# ProiectTSC_v9.net
KiCad netlist of a schematic drawn in EAGLE
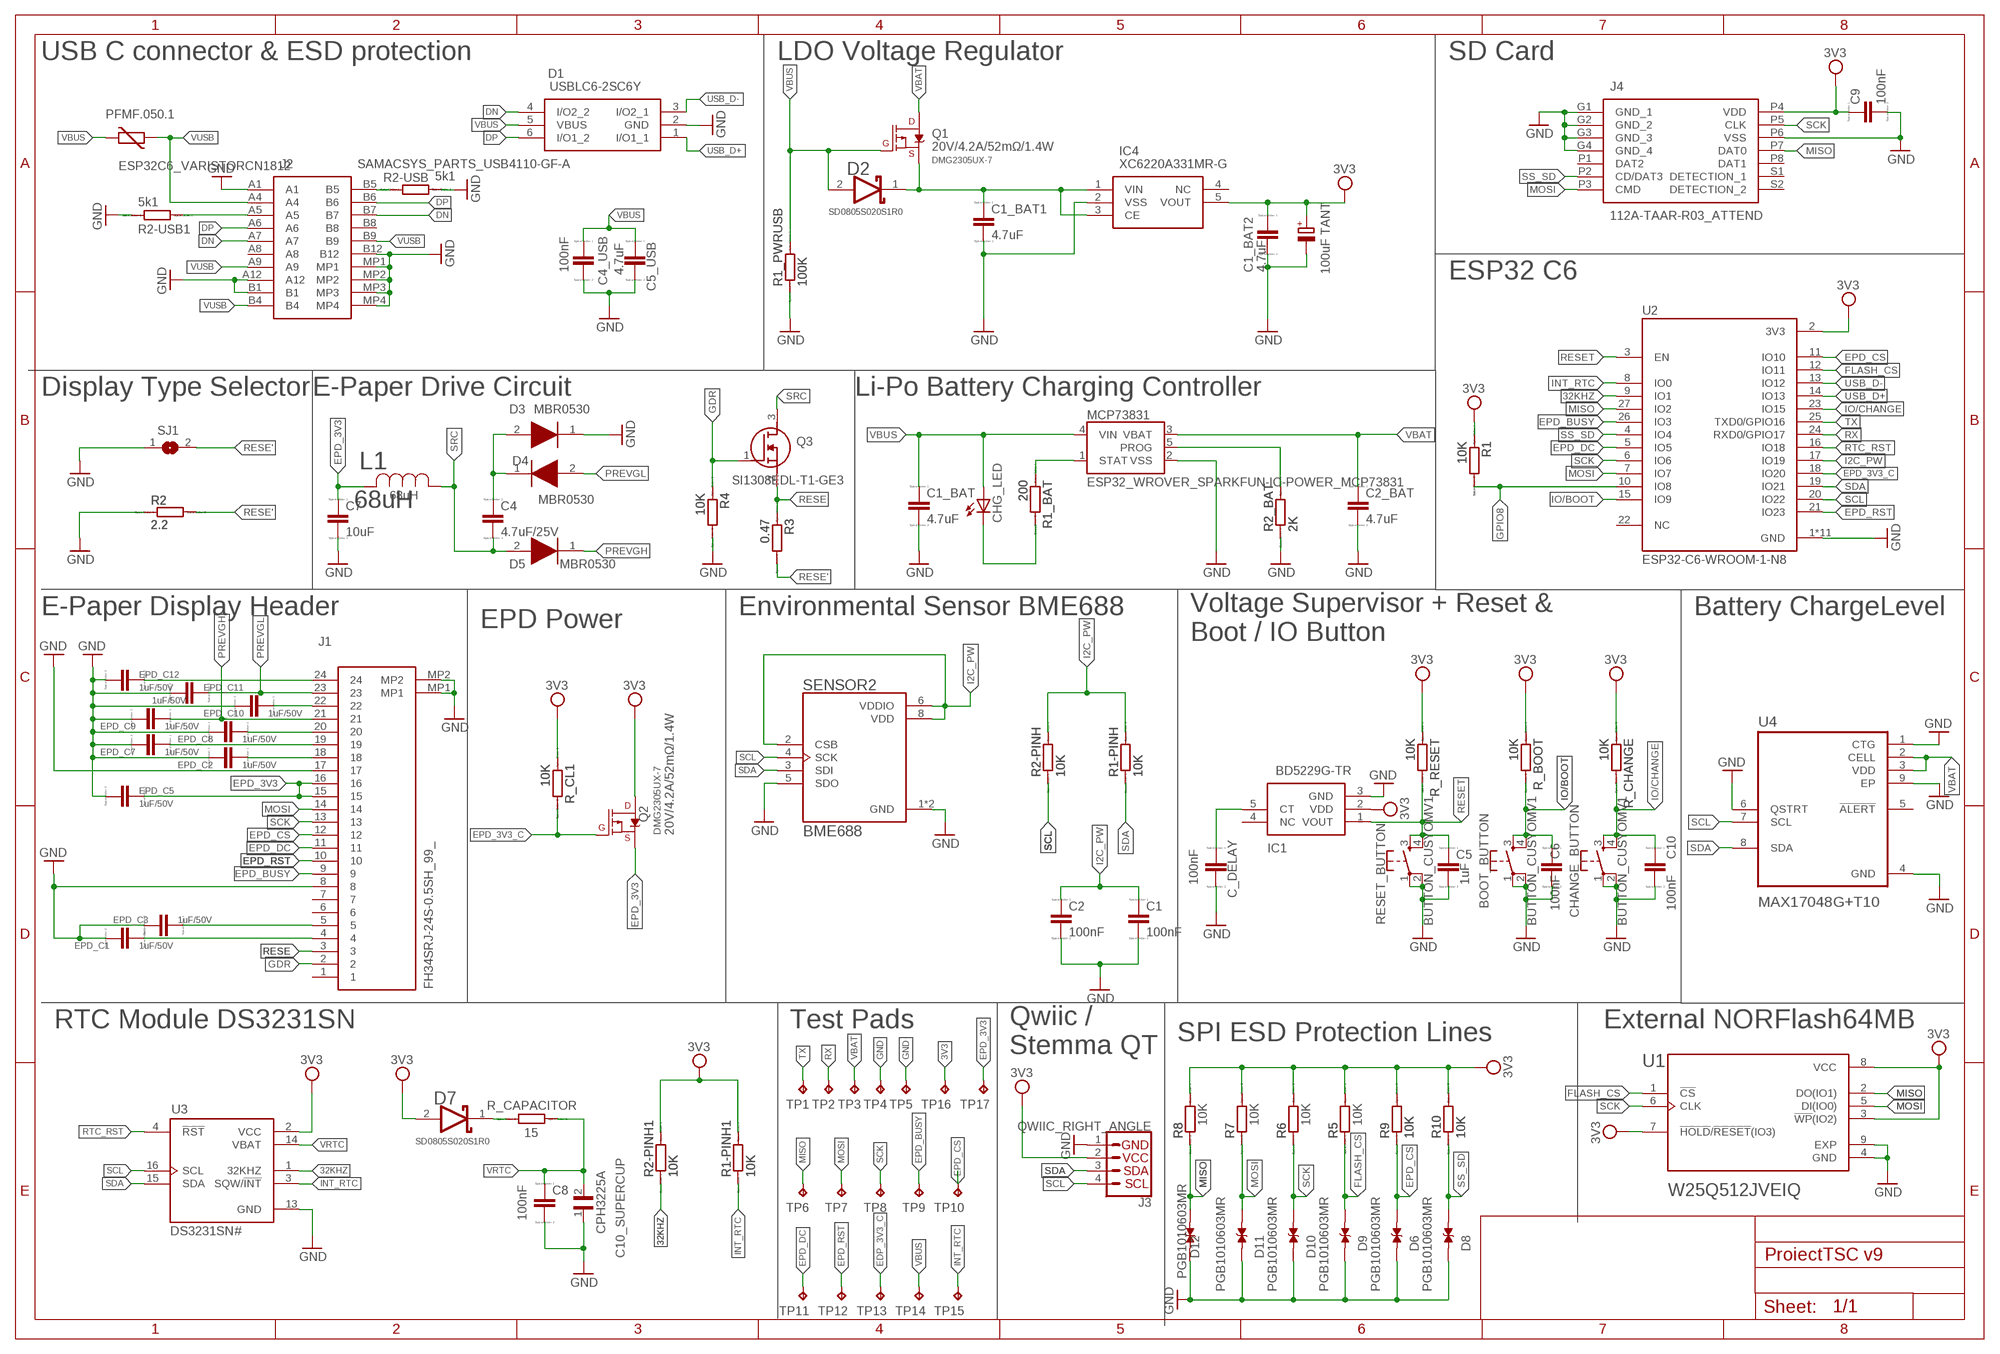
[diagram p0: schematic, sheet 1]

(export (version "E")
  (design (tool "Eeschema 10.0.6"))
  (components
    (comp (ref "BOOT_BUTTON")
      (value "BUTTON_CUSYOMV1")
      (footprint "eagle-import:MYBUTTON")
      (libsource (lib "eagle-import") (part "BUTTON_CUSYOMV1"))
    )
    (comp (ref "C1")
      (value "100nF")
      (footprint "eagle-import:EAGLE-LTSPICE_C0402")
      (libsource (lib "eagle-import") (part "EAGLE-LTSPICE_CC0402"))
    )
    (comp (ref "C1_BAT")
      (value "4.7uF")
      (footprint "eagle-import:EAGLE-LTSPICE_C0402")
      (libsource (lib "eagle-import") (part "EAGLE-LTSPICE_CC0402"))
    )
    (comp (ref "C1_BAT1")
      (value "4.7uF")
      (footprint "eagle-import:EAGLE-LTSPICE_C0402")
      (libsource (lib "eagle-import") (part "EAGLE-LTSPICE_CC0402"))
    )
    (comp (ref "C1_BAT2")
      (value "4.7uF")
      (footprint "eagle-import:EAGLE-LTSPICE_C0402")
      (libsource (lib "eagle-import") (part "EAGLE-LTSPICE_CC0402"))
    )
    (comp (ref "C2")
      (value "100nF")
      (footprint "eagle-import:EAGLE-LTSPICE_C0402")
      (libsource (lib "eagle-import") (part "EAGLE-LTSPICE_CC0402"))
    )
    (comp (ref "C2_BAT")
      (value "4.7uF")
      (footprint "eagle-import:EAGLE-LTSPICE_C0402")
      (libsource (lib "eagle-import") (part "EAGLE-LTSPICE_CC0402"))
    )
    (comp (ref "C4")
      (value "4.7uF/25V")
      (footprint "eagle-import:EAGLE-LTSPICE_C0402")
      (libsource (lib "eagle-import") (part "EAGLE-LTSPICE_CC0402"))
    )
    (comp (ref "C4_USB")
      (value "100nF")
      (footprint "eagle-import:EAGLE-LTSPICE_C0402")
      (libsource (lib "eagle-import") (part "EAGLE-LTSPICE_CC0402"))
    )
    (comp (ref "C5")
      (value "1uF")
      (footprint "eagle-import:EAGLE-LTSPICE_C0402")
      (libsource (lib "eagle-import") (part "EAGLE-LTSPICE_CC0402"))
    )
    (comp (ref "C5_USB")
      (value "4.7uF")
      (footprint "eagle-import:EAGLE-LTSPICE_C0402")
      (libsource (lib "eagle-import") (part "EAGLE-LTSPICE_CC0402"))
    )
    (comp (ref "C6")
      (value "100nF")
      (footprint "eagle-import:EAGLE-LTSPICE_C0402")
      (libsource (lib "eagle-import") (part "EAGLE-LTSPICE_CC0402"))
    )
    (comp (ref "C7")
      (value "10uF")
      (footprint "eagle-import:EAGLE-LTSPICE_C0402")
      (libsource (lib "eagle-import") (part "EAGLE-LTSPICE_CC0402"))
    )
    (comp (ref "C8")
      (value "100nF")
      (footprint "eagle-import:EAGLE-LTSPICE_C0402")
      (libsource (lib "eagle-import") (part "EAGLE-LTSPICE_CC0402"))
    )
    (comp (ref "C9")
      (value "100nF")
      (footprint "eagle-import:EAGLE-LTSPICE_C0402")
      (libsource (lib "eagle-import") (part "EAGLE-LTSPICE_CC0402"))
    )
    (comp (ref "C10")
      (value "100nF")
      (footprint "eagle-import:EAGLE-LTSPICE_C0402")
      (libsource (lib "eagle-import") (part "EAGLE-LTSPICE_CC0402"))
    )
    (comp (ref "C10_SUPERCUP")
      (value "CPH3225A")
      (footprint "eagle-import:CAPCP3225X100N")
      (fields (field (name "MF") "Seiko Instruments"))
      (libsource (lib "eagle-import") (part "CPH3225A"))
    )
    (comp (ref "CHANGE_BUTTON")
      (value "BUTTON_CUSYOMV1")
      (footprint "eagle-import:MYBUTTON")
      (libsource (lib "eagle-import") (part "BUTTON_CUSYOMV1"))
    )
    (comp (ref "CHG_LED")
      (value "ADAFRUIT_LEDCHIP-LED0603")
      (footprint "eagle-import:ADAFRUIT_CHIP-LED0603")
      (libsource (lib "eagle-import") (part "ADAFRUIT_LEDCHIP-LED0603"))
    )
    (comp (ref "C_DELAY")
      (value "100nF")
      (footprint "eagle-import:EAGLE-LTSPICE_C0402")
      (libsource (lib "eagle-import") (part "EAGLE-LTSPICE_CC0402"))
    )
    (comp (ref "D1")
      (value "USBLC6-2SC6Y")
      (footprint "eagle-import:SOT95P280X145-6N")
      (fields (field (name "MF") "STMicroelectronics"))
      (libsource (lib "eagle-import") (part "USBLC6-2SC6Y"))
    )
    (comp (ref "D2")
      (value "SD0805S020S1R0")
      (footprint "eagle-import:ESP32_WROVER_AVX---SD0805S020S1R0_AVX_SD0805S020S1R0_0")
      (fields
        (field (name "DIGIKEY_PART_NUMBER") "478-7800-1-ND")
        (field (name "MF") "AVX")
        (field (name "MOUSER_PART_NUMBER") "581-SD0805S020S1R0")
        (field (name "NUME") "SD0805S020S1R0")
      )
      (libsource (lib "eagle-import") (part "ESP32_WROVER_AVX---SD0805S020S1R0_AVX_SD0805S020S1R0_0_0AVX_SD0805S020S1R0_0_0"))
    )
    (comp (ref "D3")
      (value "MBR0530")
      (footprint "eagle-import:SOD3716X135N")
      (fields (field (name "MF") "ON Semiconductor"))
      (libsource (lib "eagle-import") (part "MBR0530"))
    )
    (comp (ref "D4")
      (value "MBR0530")
      (footprint "eagle-import:SOD3716X135N")
      (fields (field (name "MF") "ON Semiconductor"))
      (libsource (lib "eagle-import") (part "MBR0530"))
    )
    (comp (ref "D5")
      (value "MBR0530")
      (footprint "eagle-import:SOD3716X135N")
      (fields (field (name "MF") "ON Semiconductor"))
      (libsource (lib "eagle-import") (part "MBR0530"))
    )
    (comp (ref "D6")
      (value "PGB1010603MR")
      (footprint "eagle-import:DIOC1608X36N")
      (fields (field (name "MF") "Littelfuse Inc."))
      (libsource (lib "eagle-import") (part "PGB1010603MR"))
    )
    (comp (ref "D7")
      (value "SD0805S020S1R0")
      (footprint "eagle-import:ESP32_WROVER_AVX---SD0805S020S1R0_AVX_SD0805S020S1R0_0")
      (fields
        (field (name "DIGIKEY_PART_NUMBER") "478-7800-1-ND")
        (field (name "MF") "AVX")
        (field (name "MOUSER_PART_NUMBER") "581-SD0805S020S1R0")
        (field (name "MINE") "SD0805S020S1R0")
      )
      (libsource (lib "eagle-import") (part "ESP32_WROVER_AVX---SD0805S020S1R0_AVX_SD0805S020S1R0_0_0AVX_SD0805S020S1R0_0_0"))
    )
    (comp (ref "D8")
      (value "PGB1010603MR")
      (footprint "eagle-import:DIOC1608X36N")
      (fields (field (name "MF") "Littelfuse Inc."))
      (libsource (lib "eagle-import") (part "PGB1010603MR"))
    )
    (comp (ref "D9")
      (value "PGB1010603MR")
      (footprint "eagle-import:DIOC1608X36N")
      (fields (field (name "MF") "Littelfuse Inc."))
      (libsource (lib "eagle-import") (part "PGB1010603MR"))
    )
    (comp (ref "D10")
      (value "PGB1010603MR")
      (footprint "eagle-import:DIOC1608X36N")
      (fields (field (name "MF") "Littelfuse Inc."))
      (libsource (lib "eagle-import") (part "PGB1010603MR"))
    )
    (comp (ref "D11")
      (value "PGB1010603MR")
      (footprint "eagle-import:DIOC1608X36N")
      (fields (field (name "MF") "Littelfuse Inc."))
      (libsource (lib "eagle-import") (part "PGB1010603MR"))
    )
    (comp (ref "D12")
      (value "PGB1010603MR")
      (footprint "eagle-import:DIOC1608X36N")
      (fields (field (name "MF") "Littelfuse Inc."))
      (libsource (lib "eagle-import") (part "PGB1010603MR"))
    )
    (comp (ref "EPD_C1")
      (value "1uF/50V")
      (footprint "eagle-import:EAGLE-LTSPICE_C0402")
      (libsource (lib "eagle-import") (part "EAGLE-LTSPICE_CC0402"))
    )
    (comp (ref "EPD_C2")
      (value "1uF/50V")
      (footprint "eagle-import:EAGLE-LTSPICE_C0402")
      (libsource (lib "eagle-import") (part "EAGLE-LTSPICE_CC0402"))
    )
    (comp (ref "EPD_C3")
      (value "1uF/50V")
      (footprint "eagle-import:EAGLE-LTSPICE_C0402")
      (libsource (lib "eagle-import") (part "EAGLE-LTSPICE_CC0402"))
    )
    (comp (ref "EPD_C5")
      (value "1uF/50V")
      (footprint "eagle-import:EAGLE-LTSPICE_C0402")
      (libsource (lib "eagle-import") (part "EAGLE-LTSPICE_CC0402"))
    )
    (comp (ref "EPD_C7")
      (value "1uF/50V")
      (footprint "eagle-import:EAGLE-LTSPICE_C0402")
      (libsource (lib "eagle-import") (part "EAGLE-LTSPICE_CC0402"))
    )
    (comp (ref "EPD_C8")
      (value "1uF/50V")
      (footprint "eagle-import:EAGLE-LTSPICE_C0402")
      (libsource (lib "eagle-import") (part "EAGLE-LTSPICE_CC0402"))
    )
    (comp (ref "EPD_C9")
      (value "1uF/50V")
      (footprint "eagle-import:EAGLE-LTSPICE_C0402")
      (libsource (lib "eagle-import") (part "EAGLE-LTSPICE_CC0402"))
    )
    (comp (ref "EPD_C10")
      (value "1uF/50V")
      (footprint "eagle-import:EAGLE-LTSPICE_C0402")
      (libsource (lib "eagle-import") (part "EAGLE-LTSPICE_CC0402"))
    )
    (comp (ref "EPD_C11")
      (value "1uF/50V")
      (footprint "eagle-import:EAGLE-LTSPICE_C0402")
      (libsource (lib "eagle-import") (part "EAGLE-LTSPICE_CC0402"))
    )
    (comp (ref "EPD_C12")
      (value "1uF/50V")
      (footprint "eagle-import:EAGLE-LTSPICE_C0402")
      (libsource (lib "eagle-import") (part "EAGLE-LTSPICE_CC0402"))
    )
    (comp (ref "IC1")
      (value "BD5229G-TR")
      (footprint "eagle-import:SOT95P280X125-5N")
      (fields (field (name "MOUSER_PART_NUMBER") "755-BD5229G-TR"))
      (libsource (lib "eagle-import") (part "BD5229G-TR"))
    )
    (comp (ref "IC4")
      (value "XC6220A331MR-G")
      (footprint "eagle-import:SOT95P280X120-5N")
      (fields (field (name "MOUSER_PART_NUMBER") "865-XC6220A331MR-G"))
      (libsource (lib "eagle-import") (part "XC6220A331MR-G"))
    )
    (comp (ref "J1")
      (value "FH34SRJ-24S-0.5SH_99_")
      (footprint "eagle-import:FH34SRJ24S05SH99")
      (fields
        (field (name "MANUFACTURER_PART_NUMBER") "FH34SRJ-24S-0.5SH(99)")
        (field (name "MOUSER_PART_NUMBER") "798-FH34SRJ24S05SH99")
      )
      (libsource (lib "eagle-import") (part "FH34SRJ-24S-0.5SH_99_"))
    )
    (comp (ref "J2")
      (value "SAMACSYS_PARTS_USB4110-GF-A")
      (footprint "eagle-import:SAMACSYS_PARTS_USB4110GFA")
      (fields
        (field (name "MANUFACTURER_PART_NUMBER") "USB4110-GF-A")
        (field (name "MOUSER_PART_NUMBER") "640-USB4110-GF-A")
      )
      (libsource (lib "eagle-import") (part "SAMACSYS_PARTS_USB4110-GF-A"))
    )
    (comp (ref "J3")
      (value "QWIIC_RIGHT_ANGLE")
      (footprint "eagle-import:JST04_1MM_RA")
      (libsource (lib "eagle-import") (part "QWIIC_CONNECTORJS-1MM"))
    )
    (comp (ref "J4")
      (value "112A-TAAR-R03_ATTEND")
      (footprint "eagle-import:112ATAARR03ATTEND")
      (fields (field (name "MANUFACTURER_PART_NUMBER") "112A-TAAR-R03 ATTEND"))
      (libsource (lib "eagle-import") (part "112A-TAAR-R03_ATTEND"))
    )
    (comp (ref "L1")
      (value "68uH")
      (footprint "eagle-import:IND_4828-WE-TPC_WRE")
      (fields
        (field (name "MANUFACTURER_PART_NUMBER") "744043680")
        (field (name "NUME") "68uH")
        (field (name "COPYRIGHT") "Copyright (C) 2024 Ultra Librarian. All rights reserved.")
      )
      (libsource (lib "eagle-import") (part "744043680IND_4828-WE-TPC_WRE"))
    )
    (comp (ref "MCP73831")
      (value "ESP32_WROVER_SPARKFUN-IC-POWER_MCP73831")
      (footprint "eagle-import:ESP32_WROVER_SPARKFUN-IC-POWER_SOT23-5")
      (libsource (lib "eagle-import") (part "ESP32_WROVER_SPARKFUN-IC-POWER_MCP73831"))
    )
    (comp (ref "PFMF.050.1")
      (value "ESP32C6_VARISTORCN1812")
      (footprint "eagle-import:ESP32C6_VARISTOR_CT_CN1812")
      (libsource (lib "eagle-import") (part "ESP32C6_VARISTORCN1812"))
    )
    (comp (ref "Q1")
      (value "20V/4.2A/52mΩ/1.4W")
      (footprint "eagle-import:ESP32_WROVER_SPARKFUN-DISCRETESEMI_SOT23-3")
      (fields (field (name "NUME") "DMG2305UX-7"))
      (libsource (lib "eagle-import") (part "ESP32_WROVER_SPARKFUN-DISCRETESEMI_MOSFET_PCH-DMG2305UX-7"))
    )
    (comp (ref "Q2")
      (value "20V/4.2A/52mΩ/1.4W")
      (footprint "eagle-import:ESP32_WROVER_SPARKFUN-DISCRETESEMI_SOT23-3")
      (fields (field (name "MINE") "DMG2305UX-7"))
      (libsource (lib "eagle-import") (part "ESP32_WROVER_SPARKFUN-DISCRETESEMI_MOSFET_PCH-DMG2305UX-7"))
    )
    (comp (ref "Q3")
      (value "SI1308EDL-T1-GE3")
      (footprint "eagle-import:SOT65P210X110-3N")
      (fields (field (name "MF") "Vishay Siliconix"))
      (libsource (lib "eagle-import") (part "SI1308EDL-T1-GE3"))
    )
    (comp (ref "R1")
      (value "10K")
      (footprint "eagle-import:ESP32_WROVER_EAGLE-LTSPICE_R0402")
      (libsource (lib "eagle-import") (part "ESP32_WROVER_EAGLE-LTSPICE_RR0402"))
    )
    (comp (ref "R1-PINH")
      (value "10K")
      (footprint "eagle-import:ESP32_WROVER_EAGLE-LTSPICE_R0402")
      (libsource (lib "eagle-import") (part "ESP32_WROVER_EAGLE-LTSPICE_RR0402"))
    )
    (comp (ref "R1-PINH1")
      (value "10K")
      (footprint "eagle-import:ESP32_WROVER_EAGLE-LTSPICE_R0402")
      (libsource (lib "eagle-import") (part "ESP32_WROVER_EAGLE-LTSPICE_RR0402"))
    )
    (comp (ref "R1_BAT")
      (value "200")
      (footprint "eagle-import:ESP32_WROVER_EAGLE-LTSPICE_R0402")
      (libsource (lib "eagle-import") (part "ESP32_WROVER_EAGLE-LTSPICE_RR0402"))
    )
    (comp (ref "R1_PWRUSB")
      (value "100K")
      (footprint "eagle-import:ESP32_WROVER_EAGLE-LTSPICE_R0402")
      (libsource (lib "eagle-import") (part "ESP32_WROVER_EAGLE-LTSPICE_RR0402"))
    )
    (comp (ref "R2")
      (value "2.2")
      (footprint "eagle-import:ESP32_WROVER_EAGLE-LTSPICE_R0402")
      (libsource (lib "eagle-import") (part "ESP32_WROVER_EAGLE-LTSPICE_RR0402"))
    )
    (comp (ref "R2-PINH")
      (value "10K")
      (footprint "eagle-import:ESP32_WROVER_EAGLE-LTSPICE_R0402")
      (libsource (lib "eagle-import") (part "ESP32_WROVER_EAGLE-LTSPICE_RR0402"))
    )
    (comp (ref "R2-PINH1")
      (value "10K")
      (footprint "eagle-import:ESP32_WROVER_EAGLE-LTSPICE_R0402")
      (libsource (lib "eagle-import") (part "ESP32_WROVER_EAGLE-LTSPICE_RR0402"))
    )
    (comp (ref "R2-USB")
      (value "5k1")
      (footprint "eagle-import:ESP32_WROVER_EAGLE-LTSPICE_R0402")
      (libsource (lib "eagle-import") (part "ESP32_WROVER_EAGLE-LTSPICE_RR0402"))
    )
    (comp (ref "R2-USB1")
      (value "5k1")
      (footprint "eagle-import:ESP32_WROVER_EAGLE-LTSPICE_R0402")
      (libsource (lib "eagle-import") (part "ESP32_WROVER_EAGLE-LTSPICE_RR0402"))
    )
    (comp (ref "R2_BAT")
      (value "2K")
      (footprint "eagle-import:ESP32_WROVER_EAGLE-LTSPICE_R0402")
      (libsource (lib "eagle-import") (part "ESP32_WROVER_EAGLE-LTSPICE_RR0402"))
    )
    (comp (ref "R3")
      (value "0.47")
      (footprint "eagle-import:ESP32_WROVER_EAGLE-LTSPICE_R0402")
      (libsource (lib "eagle-import") (part "ESP32_WROVER_EAGLE-LTSPICE_RR0402"))
    )
    (comp (ref "R4")
      (value "10K")
      (footprint "eagle-import:ESP32_WROVER_EAGLE-LTSPICE_R0402")
      (libsource (lib "eagle-import") (part "ESP32_WROVER_EAGLE-LTSPICE_RR0402"))
    )
    (comp (ref "R5")
      (value "10K")
      (footprint "eagle-import:ESP32_WROVER_EAGLE-LTSPICE_R0402")
      (libsource (lib "eagle-import") (part "ESP32_WROVER_EAGLE-LTSPICE_RR0402"))
    )
    (comp (ref "R6")
      (value "10K")
      (footprint "eagle-import:ESP32_WROVER_EAGLE-LTSPICE_R0402")
      (libsource (lib "eagle-import") (part "ESP32_WROVER_EAGLE-LTSPICE_RR0402"))
    )
    (comp (ref "R7")
      (value "10K")
      (footprint "eagle-import:ESP32_WROVER_EAGLE-LTSPICE_R0402")
      (libsource (lib "eagle-import") (part "ESP32_WROVER_EAGLE-LTSPICE_RR0402"))
    )
    (comp (ref "R8")
      (value "10K")
      (footprint "eagle-import:ESP32_WROVER_EAGLE-LTSPICE_R0402")
      (libsource (lib "eagle-import") (part "ESP32_WROVER_EAGLE-LTSPICE_RR0402"))
    )
    (comp (ref "R9")
      (value "10K")
      (footprint "eagle-import:ESP32_WROVER_EAGLE-LTSPICE_R0402")
      (libsource (lib "eagle-import") (part "ESP32_WROVER_EAGLE-LTSPICE_RR0402"))
    )
    (comp (ref "R10")
      (value "10K")
      (footprint "eagle-import:ESP32_WROVER_EAGLE-LTSPICE_R0402")
      (libsource (lib "eagle-import") (part "ESP32_WROVER_EAGLE-LTSPICE_RR0402"))
    )
    (comp (ref "RESET_BUTTON")
      (value "BUTTON_CUSYOMV1")
      (footprint "eagle-import:MYBUTTON")
      (libsource (lib "eagle-import") (part "BUTTON_CUSYOMV1"))
    )
    (comp (ref "R_BOOT")
      (value "10K")
      (footprint "eagle-import:ESP32_WROVER_EAGLE-LTSPICE_R0402")
      (libsource (lib "eagle-import") (part "ESP32_WROVER_EAGLE-LTSPICE_RR0402"))
    )
    (comp (ref "R_CAPACITOR")
      (value "15")
      (footprint "eagle-import:ESP32_WROVER_EAGLE-LTSPICE_R0402")
      (libsource (lib "eagle-import") (part "ESP32_WROVER_EAGLE-LTSPICE_RR0402"))
    )
    (comp (ref "R_CHANGE")
      (value "10K")
      (footprint "eagle-import:ESP32_WROVER_EAGLE-LTSPICE_R0402")
      (libsource (lib "eagle-import") (part "ESP32_WROVER_EAGLE-LTSPICE_RR0402"))
    )
    (comp (ref "R_CL1")
      (value "10K")
      (footprint "eagle-import:ESP32_WROVER_EAGLE-LTSPICE_R0402")
      (libsource (lib "eagle-import") (part "ESP32_WROVER_EAGLE-LTSPICE_RR0402"))
    )
    (comp (ref "R_RESET")
      (value "10K")
      (footprint "eagle-import:ESP32_WROVER_EAGLE-LTSPICE_R0402")
      (libsource (lib "eagle-import") (part "ESP32_WROVER_EAGLE-LTSPICE_RR0402"))
    )
    (comp (ref "SENSOR2")
      (value "BME688")
      (footprint "eagle-import:ESP32_WROVER_BME680_PSON80P300X300X100-8N")
      (fields (field (name "MF") "Bosch Sensortec") (field (name "MP") "BME680"))
      (libsource (lib "eagle-import") (part "ESP32_WROVER_BME680_BME680"))
    )
    (comp (ref "SJ1") (value "SJ") (footprint "eagle-import:SJ") (libsource (lib "eagle-import") (part "SJ")))
    (comp (ref "TANT")
      (value "100uF")
      (footprint "eagle-import:RCL_CT3528")
      (libsource (lib "eagle-import") (part "RCL_CPOL-EUCT3528"))
    )
    (comp (ref "TP1")
      (value "TPTP20R")
      (footprint "eagle-import:TP20R")
      (libsource (lib "eagle-import") (part "TPTP20R"))
    )
    (comp (ref "TP2")
      (value "TPTP20R")
      (footprint "eagle-import:TP20R")
      (libsource (lib "eagle-import") (part "TPTP20R"))
    )
    (comp (ref "TP3")
      (value "TPTP20R")
      (footprint "eagle-import:TP20R")
      (libsource (lib "eagle-import") (part "TPTP20R"))
    )
    (comp (ref "TP4")
      (value "TPTP20R")
      (footprint "eagle-import:TP20R")
      (libsource (lib "eagle-import") (part "TPTP20R"))
    )
    (comp (ref "TP5")
      (value "TPTP20R")
      (footprint "eagle-import:TP20R")
      (libsource (lib "eagle-import") (part "TPTP20R"))
    )
    (comp (ref "TP6")
      (value "TPTP20R")
      (footprint "eagle-import:TP20R")
      (libsource (lib "eagle-import") (part "TPTP20R"))
    )
    (comp (ref "TP7")
      (value "TPTP20R")
      (footprint "eagle-import:TP20R")
      (libsource (lib "eagle-import") (part "TPTP20R"))
    )
    (comp (ref "TP8")
      (value "TPTP20R")
      (footprint "eagle-import:TP20R")
      (libsource (lib "eagle-import") (part "TPTP20R"))
    )
    (comp (ref "TP9")
      (value "TPTP20R")
      (footprint "eagle-import:TP20R")
      (libsource (lib "eagle-import") (part "TPTP20R"))
    )
    (comp (ref "TP10")
      (value "TPTP20R")
      (footprint "eagle-import:TP20R")
      (libsource (lib "eagle-import") (part "TPTP20R"))
    )
    (comp (ref "TP11")
      (value "TPTP20R")
      (footprint "eagle-import:TP20R")
      (libsource (lib "eagle-import") (part "TPTP20R"))
    )
    (comp (ref "TP12")
      (value "TPTP20R")
      (footprint "eagle-import:TP20R")
      (libsource (lib "eagle-import") (part "TPTP20R"))
    )
    (comp (ref "TP13")
      (value "TPTP20R")
      (footprint "eagle-import:TP20R")
      (libsource (lib "eagle-import") (part "TPTP20R"))
    )
    (comp (ref "TP14")
      (value "TPTP20R")
      (footprint "eagle-import:TP20R")
      (libsource (lib "eagle-import") (part "TPTP20R"))
    )
    (comp (ref "TP15")
      (value "TPTP20R")
      (footprint "eagle-import:TP20R")
      (libsource (lib "eagle-import") (part "TPTP20R"))
    )
    (comp (ref "TP16")
      (value "TPTP20R")
      (footprint "eagle-import:TP20R")
      (libsource (lib "eagle-import") (part "TPTP20R"))
    )
    (comp (ref "TP17")
      (value "TPTP20R")
      (footprint "eagle-import:TP20R")
      (libsource (lib "eagle-import") (part "TPTP20R"))
    )
    (comp (ref "U1")
      (value "W25Q512JVEIQ")
      (footprint "eagle-import:SON127P600X800X80-9N")
      (fields (field (name "MF") "Winbond Electronics"))
      (libsource (lib "eagle-import") (part "W25Q512JVEIQ"))
    )
    (comp (ref "U2")
      (value "ESP32-C6-WROOM-1-N8")
      (footprint "eagle-import:XCVR_ESP32-C6-WROOM-1-N8")
      (fields (field (name "MF") "Espressif Systems"))
      (libsource (lib "eagle-import") (part "ESP32-C6-WROOM-1-N8"))
    )
    (comp (ref "U3")
      (value "DS3231SN#")
      (footprint "eagle-import:SOIC127P1032X265-16N")
      (fields (field (name "MF") "Analog Devices"))
      (libsource (lib "eagle-import") (part "DS3231SN#"))
    )
    (comp (ref "U4")
      (value "MAX17048G+T10")
      (footprint "eagle-import:SON50P200X200X80-9N")
      (fields (field (name "MF") "Analog Devices"))
      (libsource (lib "eagle-import") (part "MAX17048G+T10"))
    )
  )
  (nets
    (net (code "1") (name "3V3") (class "Default")
      (node (ref "C1_BAT2") (pin "1") (pinfunction "1_1") (pintype "passive"))
      (node (ref "C9") (pin "1") (pinfunction "1_1") (pintype "passive"))
      (node (ref "D7") (pin "2") (pinfunction "ANODE_2") (pintype "bidirectional"))
      (node (ref "IC1") (pin "2") (pinfunction "VDD_2") (pintype "bidirectional"))
      (node (ref "IC4") (pin "5") (pinfunction "VOUT_5") (pintype "bidirectional"))
      (node (ref "J3") (pin "2") (pinfunction "2_2") (pintype "power_in"))
      (node (ref "J4") (pin "P4") (pinfunction "VDD_P4") (pintype "bidirectional"))
      (node (ref "Q2") (pin "3") (pinfunction "D_3") (pintype "bidirectional"))
      (node (ref "R1") (pin "1") (pinfunction "1_1") (pintype "passive"))
      (node (ref "R1-PINH1") (pin "2") (pinfunction "2_2") (pintype "passive"))
      (node (ref "R10") (pin "2") (pinfunction "2_2") (pintype "passive"))
      (node (ref "R2-PINH1") (pin "2") (pinfunction "2_2") (pintype "passive"))
      (node (ref "R5") (pin "2") (pinfunction "2_2") (pintype "passive"))
      (node (ref "R6") (pin "2") (pinfunction "2_2") (pintype "passive"))
      (node (ref "R7") (pin "2") (pinfunction "2_2") (pintype "passive"))
      (node (ref "R8") (pin "2") (pinfunction "2_2") (pintype "passive"))
      (node (ref "R9") (pin "2") (pinfunction "2_2") (pintype "passive"))
      (node (ref "R_BOOT") (pin "1") (pinfunction "1_1") (pintype "passive"))
      (node (ref "R_CHANGE") (pin "1") (pinfunction "1_1") (pintype "passive"))
      (node (ref "R_CL1") (pin "1") (pinfunction "1_1") (pintype "passive"))
      (node (ref "R_RESET") (pin "1") (pinfunction "1_1") (pintype "passive"))
      (node (ref "TANT") (pin "+") (pinfunction "+_+") (pintype "passive"))
      (node (ref "TP16") (pin "TP") (pinfunction "TP_TP") (pintype "input"))
      (node (ref "U1") (pin "3") (pinfunction "~{WP}(IO2)_3") (pintype "bidirectional"))
      (node (ref "U1") (pin "7") (pinfunction "~{HOLD}/~{RESET}(IO3)_7") (pintype "bidirectional"))
      (node (ref "U1") (pin "8") (pinfunction "VCC_8") (pintype "power_in"))
      (node (ref "U2") (pin "2") (pinfunction "3V3_2") (pintype "power_in"))
      (node (ref "U3") (pin "2") (pinfunction "VCC_2") (pintype "power_in"))
    )
    (net (code "2") (name "32KHZ") (class "Default")
      (node (ref "R2-PINH1") (pin "1") (pinfunction "1_1") (pintype "passive"))
      (node (ref "U2") (pin "9") (pinfunction "IO1_9") (pintype "bidirectional"))
      (node (ref "U3") (pin "1") (pinfunction "32KHZ_1") (pintype "output"))
    )
    (net (code "3") (name "DN") (class "Default")
      (node (ref "D1") (pin "4") (pinfunction "I/O2_2_4") (pintype "bidirectional"))
      (node (ref "J2") (pin "A7") (pinfunction "A7_A7") (pintype "bidirectional"))
      (node (ref "J2") (pin "B7") (pinfunction "B7_B7") (pintype "bidirectional"))
    )
    (net (code "4") (name "DP") (class "Default")
      (node (ref "D1") (pin "6") (pinfunction "I/O1_2_6") (pintype "bidirectional"))
      (node (ref "J2") (pin "A6") (pinfunction "A6_A6") (pintype "bidirectional"))
      (node (ref "J2") (pin "B6") (pinfunction "B6_B6") (pintype "bidirectional"))
    )
    (net (code "5") (name "EDP_3V3_C") (class "Default")
      (node (ref "TP13") (pin "TP") (pinfunction "TP_TP") (pintype "input"))
    )
    (net (code "6") (name "EPD_3V3") (class "Default")
      (node (ref "C7") (pin "1") (pinfunction "1_1") (pintype "passive"))
      (node (ref "EPD_C5") (pin "1") (pinfunction "1_1") (pintype "passive"))
      (node (ref "J1") (pin "15") (pinfunction "15_15") (pintype "bidirectional"))
      (node (ref "J1") (pin "16") (pinfunction "16_16") (pintype "bidirectional"))
      (node (ref "L1") (pin "2") (pinfunction "2_2") (pintype "passive"))
      (node (ref "Q2") (pin "2") (pinfunction "S_2") (pintype "bidirectional"))
      (node (ref "TP17") (pin "TP") (pinfunction "TP_TP") (pintype "input"))
    )
    (net (code "7") (name "EPD_3V3_C") (class "Default")
      (node (ref "Q2") (pin "1") (pinfunction "G_1") (pintype "bidirectional"))
      (node (ref "R_CL1") (pin "2") (pinfunction "2_2") (pintype "passive"))
      (node (ref "U2") (pin "18") (pinfunction "IO20_18") (pintype "bidirectional"))
    )
    (net (code "8") (name "EPD_BUSY") (class "Default")
      (node (ref "J1") (pin "9") (pinfunction "9_9") (pintype "bidirectional"))
      (node (ref "TP9") (pin "TP") (pinfunction "TP_TP") (pintype "input"))
      (node (ref "U2") (pin "26") (pinfunction "IO3_26") (pintype "bidirectional"))
    )
    (net (code "9") (name "EPD_CS") (class "Default")
      (node (ref "D6") (pin "1") (pinfunction "1_1") (pintype "passive"))
      (node (ref "J1") (pin "12") (pinfunction "12_12") (pintype "bidirectional"))
      (node (ref "R9") (pin "1") (pinfunction "1_1") (pintype "passive"))
      (node (ref "TP10") (pin "TP") (pinfunction "TP_TP") (pintype "input"))
      (node (ref "U2") (pin "11") (pinfunction "IO10_11") (pintype "bidirectional"))
    )
    (net (code "10") (name "EPD_DC") (class "Default")
      (node (ref "J1") (pin "11") (pinfunction "11_11") (pintype "bidirectional"))
      (node (ref "TP11") (pin "TP") (pinfunction "TP_TP") (pintype "input"))
      (node (ref "U2") (pin "5") (pinfunction "IO5_5") (pintype "bidirectional"))
    )
    (net (code "11") (name "EPD_RST") (class "Default")
      (node (ref "J1") (pin "10") (pinfunction "10_10") (pintype "bidirectional"))
      (node (ref "TP12") (pin "TP") (pinfunction "TP_TP") (pintype "input"))
      (node (ref "U2") (pin "21") (pinfunction "IO23_21") (pintype "bidirectional"))
    )
    (net (code "12") (name "FLASH_CS") (class "Default")
      (node (ref "D9") (pin "1") (pinfunction "1_1") (pintype "passive"))
      (node (ref "R5") (pin "1") (pinfunction "1_1") (pintype "passive"))
      (node (ref "U1") (pin "1") (pinfunction "~{CS}_1") (pintype "input"))
      (node (ref "U2") (pin "12") (pinfunction "IO11_12") (pintype "bidirectional"))
    )
    (net (code "13") (name "GDR") (class "Default")
      (node (ref "J1") (pin "2") (pinfunction "2_2") (pintype "bidirectional"))
      (node (ref "Q3") (pin "1") (pinfunction "G_1") (pintype "bidirectional"))
      (node (ref "R4") (pin "1") (pinfunction "1_1") (pintype "passive"))
    )
    (net (code "14") (name "GND") (class "Default")
      (node (ref "BOOT_BUTTON") (pin "1") (pinfunction "1_1") (pintype "passive"))
      (node (ref "BOOT_BUTTON") (pin "2") (pinfunction "2_2") (pintype "passive"))
      (node (ref "C1") (pin "2") (pinfunction "2_2") (pintype "passive"))
      (node (ref "C10") (pin "2") (pinfunction "2_2") (pintype "passive"))
      (node (ref "C10_SUPERCUP") (pin "1") (pinfunction "1_1") (pintype "passive"))
      (node (ref "C1_BAT") (pin "2") (pinfunction "2_2") (pintype "passive"))
      (node (ref "C1_BAT1") (pin "2") (pinfunction "2_2") (pintype "passive"))
      (node (ref "C1_BAT2") (pin "2") (pinfunction "2_2") (pintype "passive"))
      (node (ref "C2") (pin "2") (pinfunction "2_2") (pintype "passive"))
      (node (ref "C2_BAT") (pin "2") (pinfunction "2_2") (pintype "passive"))
      (node (ref "C4_USB") (pin "2") (pinfunction "2_2") (pintype "passive"))
      (node (ref "C5") (pin "2") (pinfunction "2_2") (pintype "passive"))
      (node (ref "C5_USB") (pin "2") (pinfunction "2_2") (pintype "passive"))
      (node (ref "C6") (pin "2") (pinfunction "2_2") (pintype "passive"))
      (node (ref "C7") (pin "2") (pinfunction "2_2") (pintype "passive"))
      (node (ref "C8") (pin "2") (pinfunction "2_2") (pintype "passive"))
      (node (ref "C9") (pin "2") (pinfunction "2_2") (pintype "passive"))
      (node (ref "CHANGE_BUTTON") (pin "1") (pinfunction "1_1") (pintype "passive"))
      (node (ref "CHANGE_BUTTON") (pin "2") (pinfunction "2_2") (pintype "passive"))
      (node (ref "C_DELAY") (pin "2") (pinfunction "2_2") (pintype "passive"))
      (node (ref "D1") (pin "2") (pinfunction "GND_2") (pintype "bidirectional"))
      (node (ref "D10") (pin "2") (pinfunction "2_2") (pintype "passive"))
      (node (ref "D11") (pin "2") (pinfunction "2_2") (pintype "passive"))
      (node (ref "D12") (pin "2") (pinfunction "2_2") (pintype "passive"))
      (node (ref "D3") (pin "1") (pinfunction "K_1") (pintype "bidirectional"))
      (node (ref "D6") (pin "2") (pinfunction "2_2") (pintype "passive"))
      (node (ref "D8") (pin "2") (pinfunction "2_2") (pintype "passive"))
      (node (ref "D9") (pin "2") (pinfunction "2_2") (pintype "passive"))
      (node (ref "EPD_C1") (pin "2") (pinfunction "2_2") (pintype "passive"))
      (node (ref "EPD_C10") (pin "2") (pinfunction "2_2") (pintype "passive"))
      (node (ref "EPD_C11") (pin "2") (pinfunction "2_2") (pintype "passive"))
      (node (ref "EPD_C12") (pin "2") (pinfunction "2_2") (pintype "passive"))
      (node (ref "EPD_C2") (pin "2") (pinfunction "2_2") (pintype "passive"))
      (node (ref "EPD_C3") (pin "2") (pinfunction "2_2") (pintype "passive"))
      (node (ref "EPD_C5") (pin "2") (pinfunction "2_2") (pintype "passive"))
      (node (ref "EPD_C7") (pin "2") (pinfunction "2_2") (pintype "passive"))
      (node (ref "EPD_C8") (pin "2") (pinfunction "2_2") (pintype "passive"))
      (node (ref "EPD_C9") (pin "2") (pinfunction "2_2") (pintype "passive"))
      (node (ref "IC1") (pin "3") (pinfunction "GND_3") (pintype "bidirectional"))
      (node (ref "IC4") (pin "2") (pinfunction "VSS_2") (pintype "bidirectional"))
      (node (ref "J1") (pin "17") (pinfunction "17_17") (pintype "bidirectional"))
      (node (ref "J1") (pin "8") (pinfunction "8_8") (pintype "bidirectional"))
      (node (ref "J1") (pin "MP1") (pinfunction "MP1_MP1") (pintype "bidirectional"))
      (node (ref "J1") (pin "MP2") (pinfunction "MP2_MP2") (pintype "bidirectional"))
      (node (ref "J2") (pin "A1") (pinfunction "A1_A1") (pintype "bidirectional"))
      (node (ref "J2") (pin "A12") (pinfunction "A12_A12") (pintype "bidirectional"))
      (node (ref "J2") (pin "B1") (pinfunction "B1_B1") (pintype "bidirectional"))
      (node (ref "J2") (pin "B12") (pinfunction "B12_B12") (pintype "bidirectional"))
      (node (ref "J2") (pin "MP1") (pinfunction "MP1_MP1") (pintype "bidirectional"))
      (node (ref "J2") (pin "MP2") (pinfunction "MP2_MP2") (pintype "bidirectional"))
      (node (ref "J2") (pin "MP3") (pinfunction "MP3_MP3") (pintype "bidirectional"))
      (node (ref "J2") (pin "MP4") (pinfunction "MP4_MP4") (pintype "bidirectional"))
      (node (ref "J3") (pin "1") (pinfunction "1_1") (pintype "power_in"))
      (node (ref "J4") (pin "G1") (pinfunction "GND_1_G1") (pintype "bidirectional"))
      (node (ref "J4") (pin "G2") (pinfunction "GND_2_G2") (pintype "bidirectional"))
      (node (ref "J4") (pin "G3") (pinfunction "GND_3_G3") (pintype "bidirectional"))
      (node (ref "J4") (pin "G4") (pinfunction "GND_4_G4") (pintype "bidirectional"))
      (node (ref "J4") (pin "P6") (pinfunction "VSS_P6") (pintype "bidirectional"))
      (node (ref "MCP73831") (pin "2") (pinfunction "VSS_2") (pintype "power_in"))
      (node (ref "R1_PWRUSB") (pin "1") (pinfunction "1_1") (pintype "passive"))
      (node (ref "R2") (pin "1") (pinfunction "1_1") (pintype "passive"))
      (node (ref "R2-USB") (pin "2") (pinfunction "2_2") (pintype "passive"))
      (node (ref "R2-USB1") (pin "1") (pinfunction "1_1") (pintype "passive"))
      (node (ref "R2_BAT") (pin "1") (pinfunction "1_1") (pintype "passive"))
      (node (ref "R4") (pin "2") (pinfunction "2_2") (pintype "passive"))
      (node (ref "RESET_BUTTON") (pin "1") (pinfunction "1_1") (pintype "passive"))
      (node (ref "RESET_BUTTON") (pin "2") (pinfunction "2_2") (pintype "passive"))
      (node (ref "SENSOR2") (pin "1") (pinfunction "GND_1") (pintype "power_in"))
      (node (ref "SENSOR2") (pin "5") (pinfunction "SDO_5") (pintype "bidirectional"))
      (node (ref "SENSOR2") (pin "7") (pinfunction "GND_7") (pintype "power_in"))
      (node (ref "SJ1") (pin "1") (pinfunction "1_1") (pintype "passive"))
      (node (ref "TANT") (pin "-") (pinfunction "-_-") (pintype "passive"))
      (node (ref "TP4") (pin "TP") (pinfunction "TP_TP") (pintype "input"))
      (node (ref "TP5") (pin "TP") (pinfunction "TP_TP") (pintype "input"))
      (node (ref "U1") (pin "4") (pinfunction "GND_4") (pintype "power_in"))
      (node (ref "U1") (pin "9") (pinfunction "EXP_9") (pintype "passive"))
      (node (ref "U2") (pin "1") (pinfunction "GND_1") (pintype "power_in"))
      (node (ref "U2") (pin "28") (pinfunction "GND_28") (pintype "power_in"))
      (node (ref "U2") (pin "29_1") (pinfunction "GND_29_1") (pintype "power_in"))
      (node (ref "U2") (pin "29_2") (pinfunction "GND_29_2") (pintype "power_in"))
      (node (ref "U2") (pin "29_3") (pinfunction "GND_29_3") (pintype "power_in"))
      (node (ref "U2") (pin "29_4") (pinfunction "GND_29_4") (pintype "power_in"))
      (node (ref "U2") (pin "29_5") (pinfunction "GND_29_5") (pintype "power_in"))
      (node (ref "U2") (pin "29_6") (pinfunction "GND_29_6") (pintype "power_in"))
      (node (ref "U2") (pin "29_7") (pinfunction "GND_29_7") (pintype "power_in"))
      (node (ref "U2") (pin "29_8") (pinfunction "GND_29_8") (pintype "power_in"))
      (node (ref "U2") (pin "29_9") (pinfunction "GND_29_9") (pintype "power_in"))
      (node (ref "U3") (pin "13") (pinfunction "GND_13") (pintype "power_in"))
      (node (ref "U4") (pin "1") (pinfunction "CTG_1") (pintype "power_in"))
      (node (ref "U4") (pin "4") (pinfunction "GND_4") (pintype "power_in"))
      (node (ref "U4") (pin "6") (pinfunction "QSTRT_6") (pintype "input"))
      (node (ref "U4") (pin "9") (pinfunction "EP_9") (pintype "power_in"))
    )
    (net (code "15") (name "GPIO8") (class "Default")
      (node (ref "R1") (pin "2") (pinfunction "2_2") (pintype "passive"))
      (node (ref "U2") (pin "10") (pinfunction "IO8_10") (pintype "bidirectional"))
    )
    (net (code "16") (name "I2C_PW") (class "Default")
      (node (ref "C1") (pin "1") (pinfunction "1_1") (pintype "passive"))
      (node (ref "C2") (pin "1") (pinfunction "1_1") (pintype "passive"))
      (node (ref "R1-PINH") (pin "2") (pinfunction "2_2") (pintype "passive"))
      (node (ref "R2-PINH") (pin "2") (pinfunction "2_2") (pintype "passive"))
      (node (ref "SENSOR2") (pin "2") (pinfunction "CSB_2") (pintype "input"))
      (node (ref "SENSOR2") (pin "6") (pinfunction "VDDIO_6") (pintype "power_in"))
      (node (ref "SENSOR2") (pin "8") (pinfunction "VDD_8") (pintype "power_in"))
      (node (ref "U2") (pin "17") (pinfunction "IO19_17") (pintype "bidirectional"))
    )
    (net (code "17") (name "INT_RTC") (class "Default")
      (node (ref "R1-PINH1") (pin "1") (pinfunction "1_1") (pintype "passive"))
      (node (ref "TP15") (pin "TP") (pinfunction "TP_TP") (pintype "input"))
      (node (ref "U2") (pin "8") (pinfunction "IO0_8") (pintype "bidirectional"))
      (node (ref "U3") (pin "3") (pinfunction "SQW/~{INT}_3") (pintype "output"))
    )
    (net (code "18") (name "IO{slash}BOOT") (class "Default")
      (node (ref "BOOT_BUTTON") (pin "3") (pinfunction "3_3") (pintype "passive"))
      (node (ref "BOOT_BUTTON") (pin "4") (pinfunction "4_4") (pintype "passive"))
      (node (ref "C6") (pin "1") (pinfunction "1_1") (pintype "passive"))
      (node (ref "R_BOOT") (pin "2") (pinfunction "2_2") (pintype "passive"))
      (node (ref "U2") (pin "15") (pinfunction "IO9_15") (pintype "bidirectional"))
    )
    (net (code "19") (name "IO{slash}CHANGE") (class "Default")
      (node (ref "C10") (pin "1") (pinfunction "1_1") (pintype "passive"))
      (node (ref "CHANGE_BUTTON") (pin "3") (pinfunction "3_3") (pintype "passive"))
      (node (ref "CHANGE_BUTTON") (pin "4") (pinfunction "4_4") (pintype "passive"))
      (node (ref "R_CHANGE") (pin "2") (pinfunction "2_2") (pintype "passive"))
      (node (ref "U2") (pin "23") (pinfunction "IO15_23") (pintype "bidirectional"))
    )
    (net (code "20") (name "MISO") (class "Default")
      (node (ref "D12") (pin "1") (pinfunction "1_1") (pintype "passive"))
      (node (ref "J4") (pin "P7") (pinfunction "DAT0_P7") (pintype "bidirectional"))
      (node (ref "R8") (pin "1") (pinfunction "1_1") (pintype "passive"))
      (node (ref "TP6") (pin "TP") (pinfunction "TP_TP") (pintype "input"))
      (node (ref "U1") (pin "2") (pinfunction "DO(IO1)_2") (pintype "bidirectional"))
      (node (ref "U2") (pin "27") (pinfunction "IO2_27") (pintype "bidirectional"))
    )
    (net (code "21") (name "MOSI") (class "Default")
      (node (ref "D11") (pin "1") (pinfunction "1_1") (pintype "passive"))
      (node (ref "J1") (pin "14") (pinfunction "14_14") (pintype "bidirectional"))
      (node (ref "J4") (pin "P3") (pinfunction "CMD_P3") (pintype "bidirectional"))
      (node (ref "R7") (pin "1") (pinfunction "1_1") (pintype "passive"))
      (node (ref "TP7") (pin "TP") (pinfunction "TP_TP") (pintype "input"))
      (node (ref "U1") (pin "5") (pinfunction "DI(IO0)_5") (pintype "bidirectional"))
      (node (ref "U2") (pin "7") (pinfunction "IO7_7") (pintype "bidirectional"))
    )
    (net (code "22") (name "Net-(CHG_LED-PadC)") (class "Default")
      (node (ref "CHG_LED") (pin "C") (pinfunction "C_C") (pintype "passive"))
      (node (ref "R1_BAT") (pin "2") (pinfunction "2_2") (pintype "passive"))
    )
    (net (code "23") (name "Net-(D2-CATHODE)") (class "Default")
      (node (ref "C1_BAT1") (pin "1") (pinfunction "1_1") (pintype "passive"))
      (node (ref "D2") (pin "1") (pinfunction "CATHODE_1") (pintype "bidirectional"))
      (node (ref "IC4") (pin "1") (pinfunction "VIN_1") (pintype "bidirectional"))
      (node (ref "IC4") (pin "3") (pinfunction "CE_3") (pintype "bidirectional"))
      (node (ref "Q1") (pin "2") (pinfunction "S_2") (pintype "bidirectional"))
    )
    (net (code "24") (name "Net-(D3-A)") (class "Default")
      (node (ref "C4") (pin "1") (pinfunction "1_1") (pintype "passive"))
      (node (ref "D3") (pin "2") (pinfunction "A_2") (pintype "bidirectional"))
      (node (ref "D4") (pin "1") (pinfunction "K_1") (pintype "bidirectional"))
    )
    (net (code "25") (name "Net-(D7-CATHODE)") (class "Default")
      (node (ref "D7") (pin "1") (pinfunction "CATHODE_1") (pintype "bidirectional"))
      (node (ref "R_CAPACITOR") (pin "2") (pinfunction "2_2") (pintype "passive"))
    )
    (net (code "26") (name "Net-(EPD_C1-Pad1)") (class "Default")
      (node (ref "EPD_C1") (pin "1") (pinfunction "1_1") (pintype "passive"))
      (node (ref "J1") (pin "4") (pinfunction "4_4") (pintype "bidirectional"))
    )
    (net (code "27") (name "Net-(EPD_C2-Pad1)") (class "Default")
      (node (ref "EPD_C2") (pin "1") (pinfunction "1_1") (pintype "passive"))
      (node (ref "J1") (pin "18") (pinfunction "18_18") (pintype "bidirectional"))
    )
    (net (code "28") (name "Net-(EPD_C3-Pad1)") (class "Default")
      (node (ref "EPD_C3") (pin "1") (pinfunction "1_1") (pintype "passive"))
      (node (ref "J1") (pin "5") (pinfunction "5_5") (pintype "bidirectional"))
    )
    (net (code "29") (name "Net-(EPD_C7-Pad1)") (class "Default")
      (node (ref "EPD_C7") (pin "1") (pinfunction "1_1") (pintype "passive"))
      (node (ref "J1") (pin "19") (pinfunction "19_19") (pintype "bidirectional"))
    )
    (net (code "30") (name "Net-(EPD_C8-Pad1)") (class "Default")
      (node (ref "EPD_C8") (pin "1") (pinfunction "1_1") (pintype "passive"))
      (node (ref "J1") (pin "20") (pinfunction "20_20") (pintype "bidirectional"))
    )
    (net (code "31") (name "Net-(EPD_C10-Pad1)") (class "Default")
      (node (ref "EPD_C10") (pin "1") (pinfunction "1_1") (pintype "passive"))
      (node (ref "J1") (pin "22") (pinfunction "22_22") (pintype "bidirectional"))
    )
    (net (code "32") (name "Net-(EPD_C12-Pad1)") (class "Default")
      (node (ref "EPD_C12") (pin "1") (pinfunction "1_1") (pintype "passive"))
      (node (ref "J1") (pin "24") (pinfunction "24_24") (pintype "bidirectional"))
    )
    (net (code "33") (name "Net-(IC1-CT)") (class "Default")
      (node (ref "C_DELAY") (pin "1") (pinfunction "1_1") (pintype "passive"))
      (node (ref "IC1") (pin "5") (pinfunction "CT_5") (pintype "bidirectional"))
    )
    (net (code "34") (name "Net-(J2-PadA5)") (class "Default")
      (node (ref "J2") (pin "A5") (pinfunction "A5_A5") (pintype "bidirectional"))
      (node (ref "R2-USB1") (pin "2") (pinfunction "2_2") (pintype "passive"))
    )
    (net (code "35") (name "Net-(J2-PadB5)") (class "Default")
      (node (ref "J2") (pin "B5") (pinfunction "B5_B5") (pintype "bidirectional"))
      (node (ref "R2-USB") (pin "1") (pinfunction "1_1") (pintype "passive"))
    )
    (net (code "36") (name "Net-(MCP73831-PROG)") (class "Default")
      (node (ref "MCP73831") (pin "5") (pinfunction "PROG_5") (pintype "input"))
      (node (ref "R2_BAT") (pin "2") (pinfunction "2_2") (pintype "passive"))
    )
    (net (code "37") (name "Net-(MCP73831-STAT)") (class "Default")
      (node (ref "MCP73831") (pin "1") (pinfunction "STAT_1") (pintype "output"))
      (node (ref "R1_BAT") (pin "1") (pinfunction "1_1") (pintype "passive"))
    )
    (net (code "38") (name "PREVGH") (class "Default")
      (node (ref "D5") (pin "1") (pinfunction "K_1") (pintype "bidirectional"))
      (node (ref "EPD_C9") (pin "1") (pinfunction "1_1") (pintype "passive"))
      (node (ref "J1") (pin "21") (pinfunction "21_21") (pintype "bidirectional"))
    )
    (net (code "39") (name "PREVGL") (class "Default")
      (node (ref "D4") (pin "2") (pinfunction "A_2") (pintype "bidirectional"))
      (node (ref "EPD_C11") (pin "1") (pinfunction "1_1") (pintype "passive"))
      (node (ref "J1") (pin "23") (pinfunction "23_23") (pintype "bidirectional"))
    )
    (net (code "40") (name "RESE") (class "Default")
      (node (ref "J1") (pin "3") (pinfunction "3_3") (pintype "bidirectional"))
      (node (ref "Q3") (pin "2") (pinfunction "S_2") (pintype "bidirectional"))
      (node (ref "R3") (pin "1") (pinfunction "1_1") (pintype "passive"))
    )
    (net (code "41") (name "RESE'") (class "Default")
      (node (ref "R2") (pin "2") (pinfunction "2_2") (pintype "passive"))
      (node (ref "R3") (pin "2") (pinfunction "2_2") (pintype "passive"))
      (node (ref "SJ1") (pin "2") (pinfunction "2_2") (pintype "passive"))
    )
    (net (code "42") (name "RESET") (class "Default")
      (node (ref "C5") (pin "1") (pinfunction "1_1") (pintype "passive"))
      (node (ref "IC1") (pin "1") (pinfunction "VOUT_1") (pintype "bidirectional"))
      (node (ref "RESET_BUTTON") (pin "3") (pinfunction "3_3") (pintype "passive"))
      (node (ref "RESET_BUTTON") (pin "4") (pinfunction "4_4") (pintype "passive"))
      (node (ref "R_RESET") (pin "2") (pinfunction "2_2") (pintype "passive"))
      (node (ref "U2") (pin "3") (pinfunction "EN_3") (pintype "input"))
    )
    (net (code "43") (name "RTC_RST") (class "Default")
      (node (ref "U2") (pin "16") (pinfunction "IO18_16") (pintype "bidirectional"))
      (node (ref "U3") (pin "4") (pinfunction "~{RST}_4") (pintype "input"))
    )
    (net (code "44") (name "RX") (class "Default")
      (node (ref "TP2") (pin "TP") (pinfunction "TP_TP") (pintype "input"))
      (node (ref "U2") (pin "24") (pinfunction "RXD0/GPIO17_24") (pintype "bidirectional"))
    )
    (net (code "45") (name "SCK") (class "Default")
      (node (ref "D10") (pin "1") (pinfunction "1_1") (pintype "passive"))
      (node (ref "J1") (pin "13") (pinfunction "13_13") (pintype "bidirectional"))
      (node (ref "J4") (pin "P5") (pinfunction "CLK_P5") (pintype "bidirectional"))
      (node (ref "R6") (pin "1") (pinfunction "1_1") (pintype "passive"))
      (node (ref "TP8") (pin "TP") (pinfunction "TP_TP") (pintype "input"))
      (node (ref "U1") (pin "6") (pinfunction "CLK_6") (pintype "input"))
      (node (ref "U2") (pin "6") (pinfunction "IO6_6") (pintype "bidirectional"))
    )
    (net (code "46") (name "SCL") (class "Default")
      (node (ref "J3") (pin "4") (pinfunction "4_4") (pintype "passive"))
      (node (ref "R2-PINH") (pin "1") (pinfunction "1_1") (pintype "passive"))
      (node (ref "SENSOR2") (pin "4") (pinfunction "SCK_4") (pintype "input"))
      (node (ref "U2") (pin "20") (pinfunction "IO22_20") (pintype "bidirectional"))
      (node (ref "U3") (pin "16") (pinfunction "SCL_16") (pintype "input"))
      (node (ref "U4") (pin "7") (pinfunction "SCL_7") (pintype "input"))
    )
    (net (code "47") (name "SDA") (class "Default")
      (node (ref "J3") (pin "3") (pinfunction "3_3") (pintype "passive"))
      (node (ref "R1-PINH") (pin "1") (pinfunction "1_1") (pintype "passive"))
      (node (ref "SENSOR2") (pin "3") (pinfunction "SDI_3") (pintype "bidirectional"))
      (node (ref "U2") (pin "19") (pinfunction "IO21_19") (pintype "bidirectional"))
      (node (ref "U3") (pin "15") (pinfunction "SDA_15") (pintype "bidirectional"))
      (node (ref "U4") (pin "8") (pinfunction "SDA_8") (pintype "bidirectional"))
    )
    (net (code "48") (name "SRC") (class "Default")
      (node (ref "C4") (pin "2") (pinfunction "2_2") (pintype "passive"))
      (node (ref "D5") (pin "2") (pinfunction "A_2") (pintype "bidirectional"))
      (node (ref "L1") (pin "1") (pinfunction "1_1") (pintype "passive"))
      (node (ref "Q3") (pin "3") (pinfunction "D_3") (pintype "bidirectional"))
    )
    (net (code "49") (name "SS_SD") (class "Default")
      (node (ref "D8") (pin "1") (pinfunction "1_1") (pintype "passive"))
      (node (ref "J4") (pin "P2") (pinfunction "CD/DAT3_P2") (pintype "bidirectional"))
      (node (ref "R10") (pin "1") (pinfunction "1_1") (pintype "passive"))
      (node (ref "U2") (pin "4") (pinfunction "IO4_4") (pintype "bidirectional"))
    )
    (net (code "50") (name "TX") (class "Default")
      (node (ref "TP1") (pin "TP") (pinfunction "TP_TP") (pintype "input"))
      (node (ref "U2") (pin "25") (pinfunction "TXD0/GPIO16_25") (pintype "bidirectional"))
    )
    (net (code "51") (name "USB_D+") (class "Default")
      (node (ref "D1") (pin "1") (pinfunction "I/O1_1_1") (pintype "bidirectional"))
      (node (ref "U2") (pin "14") (pinfunction "IO13_14") (pintype "bidirectional"))
    )
    (net (code "52") (name "USB_D-") (class "Default")
      (node (ref "D1") (pin "3") (pinfunction "I/O2_1_3") (pintype "bidirectional"))
      (node (ref "U2") (pin "13") (pinfunction "IO12_13") (pintype "bidirectional"))
    )
    (net (code "53") (name "VBAT") (class "Default")
      (node (ref "C2_BAT") (pin "1") (pinfunction "1_1") (pintype "passive"))
      (node (ref "MCP73831") (pin "3") (pinfunction "VBAT_3") (pintype "power_in"))
      (node (ref "Q1") (pin "3") (pinfunction "D_3") (pintype "bidirectional"))
      (node (ref "TP3") (pin "TP") (pinfunction "TP_TP") (pintype "input"))
      (node (ref "U4") (pin "2") (pinfunction "CELL_2") (pintype "power_in"))
      (node (ref "U4") (pin "3") (pinfunction "VDD_3") (pintype "power_in"))
    )
    (net (code "54") (name "VBUS") (class "Default")
      (node (ref "C1_BAT") (pin "1") (pinfunction "1_1") (pintype "passive"))
      (node (ref "C4_USB") (pin "1") (pinfunction "1_1") (pintype "passive"))
      (node (ref "C5_USB") (pin "1") (pinfunction "1_1") (pintype "passive"))
      (node (ref "CHG_LED") (pin "A") (pinfunction "A_A") (pintype "passive"))
      (node (ref "D1") (pin "5") (pinfunction "VBUS_5") (pintype "bidirectional"))
      (node (ref "D2") (pin "2") (pinfunction "ANODE_2") (pintype "bidirectional"))
      (node (ref "MCP73831") (pin "4") (pinfunction "VIN_4") (pintype "power_in"))
      (node (ref "PFMF.050.1") (pin "2") (pinfunction "2_2") (pintype "passive"))
      (node (ref "Q1") (pin "1") (pinfunction "G_1") (pintype "bidirectional"))
      (node (ref "R1_PWRUSB") (pin "2") (pinfunction "2_2") (pintype "passive"))
      (node (ref "TP14") (pin "TP") (pinfunction "TP_TP") (pintype "input"))
    )
    (net (code "55") (name "VRTC") (class "Default")
      (node (ref "C10_SUPERCUP") (pin "2") (pinfunction "2_2") (pintype "passive"))
      (node (ref "C8") (pin "1") (pinfunction "1_1") (pintype "passive"))
      (node (ref "R_CAPACITOR") (pin "1") (pinfunction "1_1") (pintype "passive"))
      (node (ref "U3") (pin "14") (pinfunction "VBAT_14") (pintype "power_in"))
    )
    (net (code "56") (name "VUSB") (class "Default")
      (node (ref "J2") (pin "A4") (pinfunction "A4_A4") (pintype "bidirectional"))
      (node (ref "J2") (pin "A9") (pinfunction "A9_A9") (pintype "bidirectional"))
      (node (ref "J2") (pin "B4") (pinfunction "B4_B4") (pintype "bidirectional"))
      (node (ref "J2") (pin "B9") (pinfunction "B9_B9") (pintype "bidirectional"))
      (node (ref "PFMF.050.1") (pin "1") (pinfunction "1_1") (pintype "passive"))
    )
    (net (code "57") (name "unconnected-(IC1-NC-Pad4)") (class "Default")
      (node (ref "IC1") (pin "4") (pinfunction "NC_4") (pintype "no_connect"))
    )
    (net (code "58") (name "unconnected-(IC4-NC-Pad4)") (class "Default")
      (node (ref "IC4") (pin "4") (pinfunction "NC_4") (pintype "no_connect"))
    )
    (net (code "59") (name "unconnected-(J1-Pad1)") (class "Default")
      (node (ref "J1") (pin "1") (pinfunction "1_1") (pintype "bidirectional"))
    )
    (net (code "60") (name "unconnected-(J1-Pad6)") (class "Default")
      (node (ref "J1") (pin "6") (pinfunction "6_6") (pintype "bidirectional"))
    )
    (net (code "61") (name "unconnected-(J1-Pad7)") (class "Default")
      (node (ref "J1") (pin "7") (pinfunction "7_7") (pintype "bidirectional"))
    )
    (net (code "62") (name "unconnected-(J2-PadA8)") (class "Default")
      (node (ref "J2") (pin "A8") (pinfunction "A8_A8") (pintype "bidirectional"))
    )
    (net (code "63") (name "unconnected-(J2-PadB8)") (class "Default")
      (node (ref "J2") (pin "B8") (pinfunction "B8_B8") (pintype "bidirectional"))
    )
    (net (code "64") (name "unconnected-(J4-DAT1-PadP8)") (class "Default")
      (node (ref "J4") (pin "P8") (pinfunction "DAT1_P8") (pintype "bidirectional"))
    )
    (net (code "65") (name "unconnected-(J4-DAT2-PadP1)") (class "Default")
      (node (ref "J4") (pin "P1") (pinfunction "DAT2_P1") (pintype "bidirectional"))
    )
    (net (code "66") (name "unconnected-(J4-DETECTION_1-PadS1)") (class "Default")
      (node (ref "J4") (pin "S1") (pinfunction "DETECTION_1_S1") (pintype "bidirectional"))
    )
    (net (code "67") (name "unconnected-(J4-DETECTION_2-PadS2)") (class "Default")
      (node (ref "J4") (pin "S2") (pinfunction "DETECTION_2_S2") (pintype "bidirectional"))
    )
    (net (code "68") (name "unconnected-(U2-NC-Pad22)") (class "Default")
      (node (ref "U2") (pin "22") (pinfunction "NC_22") (pintype "no_connect"))
    )
    (net (code "69") (name "unconnected-(U4-~{ALERT}-Pad5)") (class "Default")
      (node (ref "U4") (pin "5") (pinfunction "~{ALERT}_5") (pintype "output"))
    )
  )
)
